# WEN-OP-AD8367.net
KiCad netlist of a schematic drawn in EasyEDA Pro
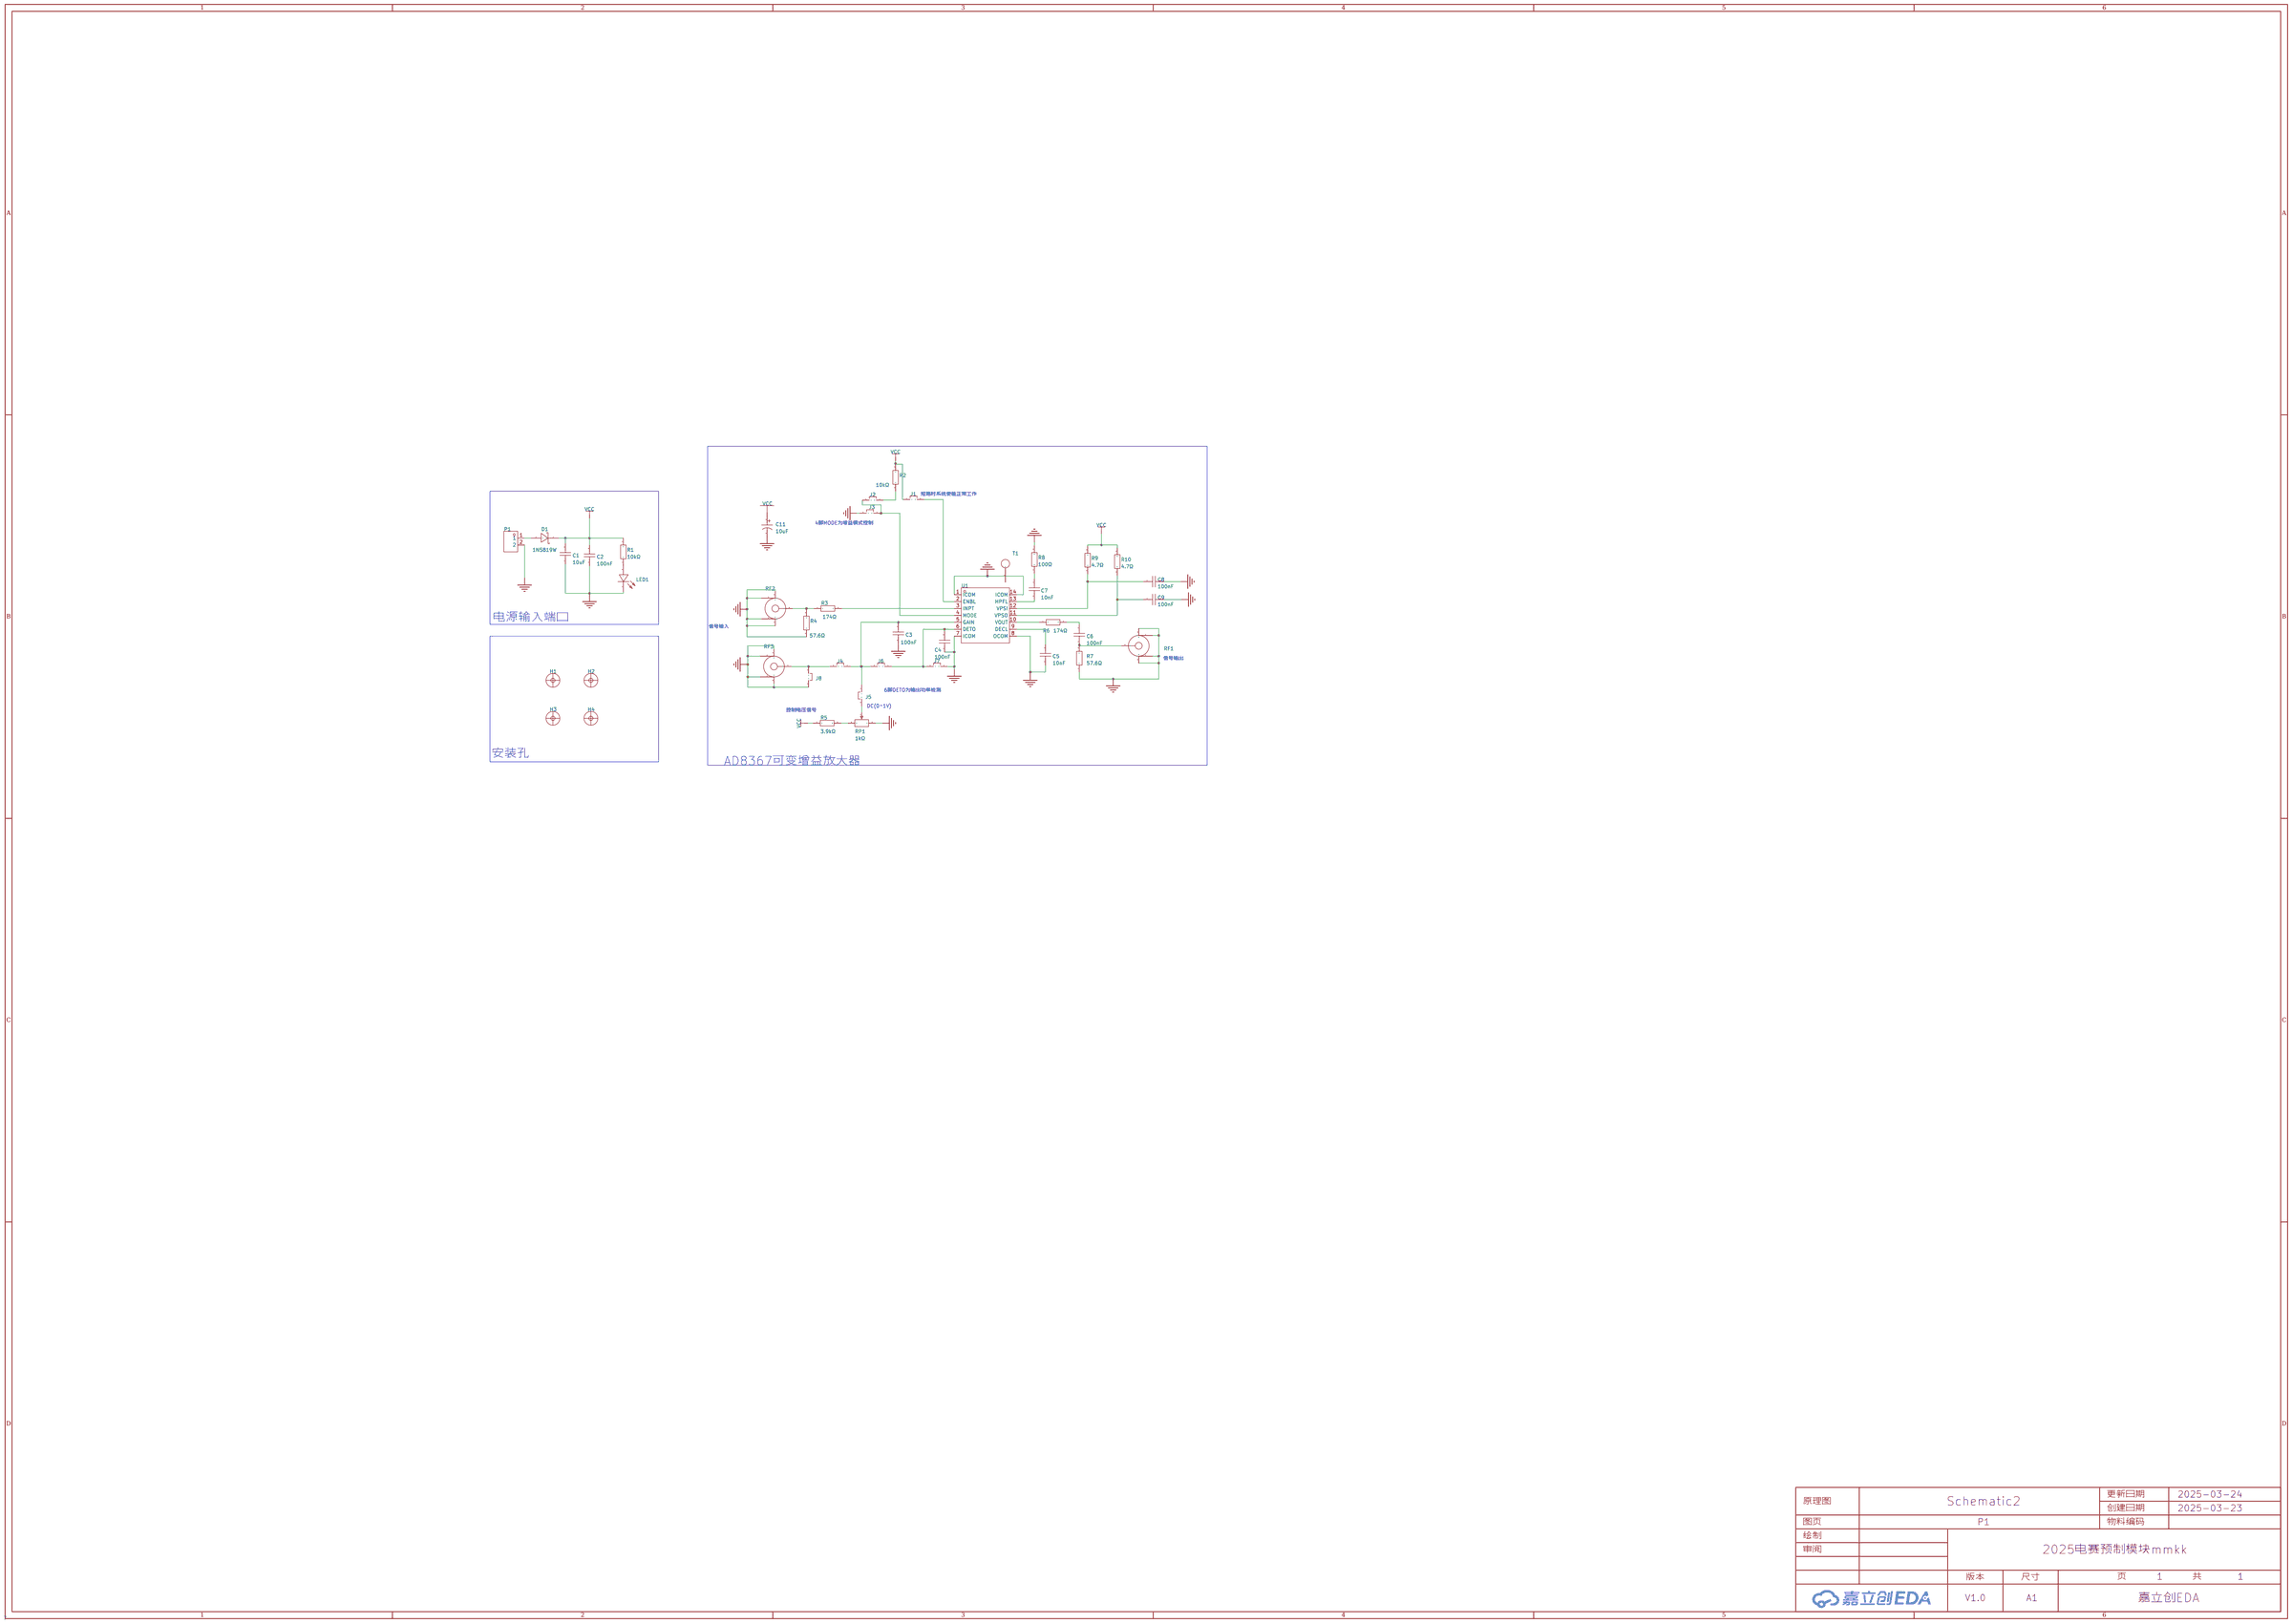
[diagram p0: schematic sheet]

(export (version "E")
  (design (tool "Eeschema 10.0.6"))
  (components
    (comp (ref "C1")
      (value "10uF")
      (footprint "easyedapro:C0805")
      (description "容值:10uF;精度:±10%;额定电压:25V;材质(温度系数):X5R;")
      (fields
        (field (name "Manufacturer Part") "CL21A106KAYNNNE")
        (field (name "Manufacturer") "SAMSUNG(三星)")
      )
      (libsource (lib "easyedapro") (part "CL21A106KAYNNNE"))
    )
    (comp (ref "C2")
      (value "100nF")
      (footprint "easyedapro:C0805")
      (description "容值:100nF;精度:±10%;额定电压:100V;材质(温度系数):X7R;")
      (fields
        (field (name "Manufacturer Part") "CL21B104KCFNNNE")
        (field (name "Manufacturer") "SAMSUNG(三星)")
      )
      (libsource (lib "easyedapro") (part "CL21B104KCFNNNE"))
    )
    (comp (ref "C3")
      (value "100nF")
      (footprint "easyedapro:C0805")
      (description "容值:100nF;精度:±10%;额定电压:100V;材质(温度系数):X7R;")
      (fields
        (field (name "Manufacturer Part") "CL21B104KCFNNNE")
        (field (name "Manufacturer") "SAMSUNG(三星)")
      )
      (libsource (lib "easyedapro") (part "CL21B104KCFNNNE"))
    )
    (comp (ref "C4")
      (value "100nF")
      (footprint "easyedapro:C0805")
      (description "容值:100nF;精度:±10%;额定电压:100V;材质(温度系数):X7R;")
      (fields
        (field (name "Manufacturer Part") "CL21B104KCFNNNE")
        (field (name "Manufacturer") "SAMSUNG(三星)")
      )
      (libsource (lib "easyedapro") (part "CL21B104KCFNNNE"))
    )
    (comp (ref "C5")
      (value "10nF")
      (footprint "easyedapro:C0805")
      (description "容值:10nF;精度:±10%;额定电压:50V;材质(温度系数):X7R;")
      (fields
        (field (name "Manufacturer Part") "CL21B103KBANNNC")
        (field (name "Manufacturer") "SAMSUNG(三星)")
      )
      (libsource (lib "easyedapro") (part "CL21B103KBANNNC"))
    )
    (comp (ref "C6")
      (value "100nF")
      (footprint "easyedapro:C0805")
      (description "容值:100nF;精度:±10%;额定电压:100V;材质(温度系数):X7R;")
      (fields
        (field (name "Manufacturer Part") "CL21B104KCFNNNE")
        (field (name "Manufacturer") "SAMSUNG(三星)")
      )
      (libsource (lib "easyedapro") (part "CL21B104KCFNNNE"))
    )
    (comp (ref "C7")
      (value "10nF")
      (footprint "easyedapro:C0805")
      (description "容值:10nF;精度:±10%;额定电压:50V;材质(温度系数):X7R;")
      (fields
        (field (name "Manufacturer Part") "CL21B103KBANNNC")
        (field (name "Manufacturer") "SAMSUNG(三星)")
      )
      (libsource (lib "easyedapro") (part "CL21B103KBANNNC"))
    )
    (comp (ref "C8")
      (value "100nF")
      (footprint "easyedapro:C0805")
      (description "容值:100nF;精度:±10%;额定电压:100V;材质(温度系数):X7R;")
      (fields
        (field (name "Manufacturer Part") "CL21B104KCFNNNE")
        (field (name "Manufacturer") "SAMSUNG(三星)")
      )
      (libsource (lib "easyedapro") (part "CL21B104KCFNNNE"))
    )
    (comp (ref "C9")
      (value "100nF")
      (footprint "easyedapro:C0805")
      (description "容值:100nF;精度:±10%;额定电压:100V;材质(温度系数):X7R;")
      (fields
        (field (name "Manufacturer Part") "CL21B104KCFNNNE")
        (field (name "Manufacturer") "SAMSUNG(三星)")
      )
      (libsource (lib "easyedapro") (part "CL21B104KCFNNNE"))
    )
    (comp (ref "C11")
      (value "10uF")
      (footprint "easyedapro:CAP-SMD_BD4.0-L4.3-W4.3-FD")
      (fields (field (name "Manufacturer Part") "CS1C100M-CRC54") (field (name "Manufacturer") "ST(先科)"))
      (libsource (lib "easyedapro") (part "CS1C100M-CRC54"))
    )
    (comp (ref "D1")
      (value "1N5819W")
      (footprint "easyedapro:SOD-123F_L2.8-W1.8-LS3.7-RD")
      (description "直流反向耐压(Vr):40V;平均整流电流(Io):1A;正向压降(Vf):600mV@1A;")
      (fields (field (name "Manufacturer") "晶导微电子"))
      (libsource (lib "easyedapro") (part "1N5819W"))
    )
    (comp (ref "H1")
      (value "~")
      (footprint "easyedapro:M3")
      (fields (field (name "Manufacturer Part") "M3x10+6") (field (name "Manufacturer") "Shuntian(顺天五金)"))
      (libsource (lib "easyedapro") (part "M3"))
    )
    (comp (ref "H2")
      (value "~")
      (footprint "easyedapro:M3")
      (fields (field (name "Manufacturer Part") "M3x10+6") (field (name "Manufacturer") "Shuntian(顺天五金)"))
      (libsource (lib "easyedapro") (part "M3"))
    )
    (comp (ref "H3")
      (value "~")
      (footprint "easyedapro:M3")
      (fields (field (name "Manufacturer Part") "M3x10+6") (field (name "Manufacturer") "Shuntian(顺天五金)"))
      (libsource (lib "easyedapro") (part "M3"))
    )
    (comp (ref "H4")
      (value "~")
      (footprint "easyedapro:M3")
      (fields (field (name "Manufacturer Part") "M3x10+6") (field (name "Manufacturer") "Shuntian(顺天五金)"))
      (libsource (lib "easyedapro") (part "M3"))
    )
    (comp (ref "J1")
      (value "PZ254V-11-02P")
      (footprint "easyedapro:HDR-TH_2P-P2.54-V-M")
      (fields (field (name "Manufacturer") "XFCN(兴飞)"))
      (libsource (lib "easyedapro") (part "PZ254V-11-02P"))
    )
    (comp (ref "J2")
      (value "PZ254V-11-02P")
      (footprint "easyedapro:HDR-TH_2P-P2.54-V-M")
      (fields (field (name "Manufacturer") "XFCN(兴飞)"))
      (libsource (lib "easyedapro") (part "PZ254V-11-02P"))
    )
    (comp (ref "J3")
      (value "PZ254V-11-02P")
      (footprint "easyedapro:HDR-TH_2P-P2.54-V-M")
      (fields (field (name "Manufacturer") "XFCN(兴飞)"))
      (libsource (lib "easyedapro") (part "PZ254V-11-02P"))
    )
    (comp (ref "J4")
      (value "PZ254V-11-02P")
      (footprint "easyedapro:HDR-TH_2P-P2.54-V-M")
      (fields (field (name "Manufacturer") "XFCN(兴飞)"))
      (libsource (lib "easyedapro") (part "PZ254V-11-02P"))
    )
    (comp (ref "J5")
      (value "PZ254V-11-02P")
      (footprint "easyedapro:HDR-TH_2P-P2.54-V-M")
      (fields (field (name "Manufacturer") "XFCN(兴飞)"))
      (libsource (lib "easyedapro") (part "PZ254V-11-02P"))
    )
    (comp (ref "J6")
      (value "PZ254V-11-02P")
      (footprint "easyedapro:HDR-TH_2P-P2.54-V-M")
      (fields (field (name "Manufacturer") "XFCN(兴飞)"))
      (libsource (lib "easyedapro") (part "PZ254V-11-02P"))
    )
    (comp (ref "J7")
      (value "PZ254V-11-02P")
      (footprint "easyedapro:HDR-TH_2P-P2.54-V-M")
      (fields (field (name "Manufacturer") "XFCN(兴飞)"))
      (libsource (lib "easyedapro") (part "PZ254V-11-02P"))
    )
    (comp (ref "J8")
      (value "PZ254V-11-02P")
      (footprint "easyedapro:HDR-TH_2P-P2.54-V-M")
      (fields (field (name "Manufacturer") "XFCN(兴飞)"))
      (libsource (lib "easyedapro") (part "PZ254V-11-02P"))
    )
    (comp (ref "LED1")
      (value "NCD0805R1")
      (footprint "easyedapro:LED0805-RD_RED")
      (description "发光颜色:红灯;")
      (fields (field (name "Manufacturer") "国星光电"))
      (libsource (lib "easyedapro") (part "FC-2012HRK-620D"))
    )
    (comp (ref "P1")
      (value "KF301-5.0-2P")
      (footprint "easyedapro:CONN-TH_P5.00_KF301-5.0-2P")
      (fields (field (name "Manufacturer") "KEFA(科发)"))
      (libsource (lib "easyedapro") (part "KF301-5.0-2P"))
    )
    (comp (ref "R1")
      (value "10kΩ")
      (footprint "easyedapro:R0805")
      (description "电阻类型:厚膜电阻;阻值:10kΩ;精度:±1%;功率:125mW;")
      (fields
        (field (name "Manufacturer Part") "0805W8F1002T5E")
        (field (name "Manufacturer") "UNI-ROYAL(厚声)")
      )
      (libsource (lib "easyedapro") (part "0805W8F1002T5E"))
    )
    (comp (ref "R2")
      (value "10kΩ")
      (footprint "easyedapro:R0805")
      (description "电阻类型:厚膜电阻;阻值:10kΩ;精度:±1%;功率:125mW;")
      (fields
        (field (name "Manufacturer Part") "0805W8F1002T5E")
        (field (name "Manufacturer") "UNI-ROYAL(厚声)")
      )
      (libsource (lib "easyedapro") (part "0805W8F1002T5E"))
    )
    (comp (ref "R3")
      (value "174Ω")
      (footprint "easyedapro:R0805")
      (description "电阻类型:厚膜电阻;阻值:174Ω;精度:±1%;功率:125mW;")
      (fields
        (field (name "Manufacturer Part") "0805W8F1740T5E")
        (field (name "Manufacturer") "UNI-ROYAL(厚声)")
      )
      (libsource (lib "easyedapro") (part "0805W8F1740T5E"))
    )
    (comp (ref "R4")
      (value "57.6Ω")
      (footprint "easyedapro:R0805")
      (description "电阻类型:厚膜电阻;阻值:57.6Ω;精度:±1%;功率:125mW;")
      (fields
        (field (name "Manufacturer Part") "0805W8F576JT5E")
        (field (name "Manufacturer") "UNI-ROYAL(厚声)")
      )
      (libsource (lib "easyedapro") (part "0805W8F576JT5E"))
    )
    (comp (ref "R5")
      (value "3.9kΩ")
      (footprint "easyedapro:R0805")
      (description "电阻类型:厚膜电阻;阻值:3.9kΩ;精度:±1%;功率:125mW;")
      (fields
        (field (name "Manufacturer Part") "0805W8F3901T5E")
        (field (name "Manufacturer") "UNI-ROYAL(厚声)")
      )
      (libsource (lib "easyedapro") (part "0805W8F3901T5E"))
    )
    (comp (ref "R6")
      (value "174Ω")
      (footprint "easyedapro:R0805")
      (description "电阻类型:厚膜电阻;阻值:174Ω;精度:±1%;功率:125mW;")
      (fields
        (field (name "Manufacturer Part") "0805W8F1740T5E")
        (field (name "Manufacturer") "UNI-ROYAL(厚声)")
      )
      (libsource (lib "easyedapro") (part "0805W8F1740T5E"))
    )
    (comp (ref "R7")
      (value "57.6Ω")
      (footprint "easyedapro:R0805")
      (description "电阻类型:厚膜电阻;阻值:57.6Ω;精度:±1%;功率:125mW;")
      (fields
        (field (name "Manufacturer Part") "0805W8F576JT5E")
        (field (name "Manufacturer") "UNI-ROYAL(厚声)")
      )
      (libsource (lib "easyedapro") (part "0805W8F576JT5E"))
    )
    (comp (ref "R8")
      (value "100Ω")
      (footprint "easyedapro:R0805")
      (description "电阻类型:厚膜电阻;阻值:100Ω;精度:±1%;功率:125mW;")
      (fields
        (field (name "Manufacturer Part") "0805W8F1000T5E")
        (field (name "Manufacturer") "UNI-ROYAL(厚声)")
      )
      (libsource (lib "easyedapro") (part "0805W8F1000T5E"))
    )
    (comp (ref "R9")
      (value "4.7Ω")
      (footprint "easyedapro:R0805")
      (description "电阻类型:厚膜电阻;阻值:4.7Ω;精度:±1%;功率:125mW;")
      (fields
        (field (name "Manufacturer Part") "0805W8F470KT5E")
        (field (name "Manufacturer") "UNI-ROYAL(厚声)")
      )
      (libsource (lib "easyedapro") (part "0805W8F470KT5E"))
    )
    (comp (ref "R10")
      (value "4.7Ω")
      (footprint "easyedapro:R0805")
      (description "电阻类型:厚膜电阻;阻值:4.7Ω;精度:±1%;功率:125mW;")
      (fields
        (field (name "Manufacturer Part") "0805W8F470KT5E")
        (field (name "Manufacturer") "UNI-ROYAL(厚声)")
      )
      (libsource (lib "easyedapro") (part "0805W8F470KT5E"))
    )
    (comp (ref "RF1")
      (value "BWSMA-KE-P001")
      (footprint "easyedapro:SMA-SMD_BWSMA-KE-P001")
      (description "连接器类型:板端;射频系列:SMA;接口类型:内孔;端口数量:1;阻抗:50Ω;频率-最大值:12.4GHz;样式:偏脚;接口直径:5.2mm;接口长度/高度:-;工作温度范围:-;")
      (fields (field (name "Manufacturer") "BAT WIRELESS(蝙蝠无线)"))
      (libsource (lib "easyedapro") (part "BWSMA-KE-P001"))
    )
    (comp (ref "RF2")
      (value "BWSMA-KE-P001")
      (footprint "easyedapro:SMA-SMD_BWSMA-KE-P001")
      (description "连接器类型:板端;射频系列:SMA;接口类型:内孔;端口数量:1;阻抗:50Ω;频率-最大值:12.4GHz;样式:偏脚;接口直径:5.2mm;接口长度/高度:-;工作温度范围:-;")
      (fields (field (name "Manufacturer") "BAT WIRELESS(蝙蝠无线)"))
      (libsource (lib "easyedapro") (part "BWSMA-KE-P001"))
    )
    (comp (ref "RF3")
      (value "BWSMA-KE-P001")
      (footprint "easyedapro:SMA-SMD_BWSMA-KE-P001")
      (description "连接器类型:板端;射频系列:SMA;接口类型:内孔;端口数量:1;阻抗:50Ω;频率-最大值:12.4GHz;样式:偏脚;接口直径:5.2mm;接口长度/高度:-;工作温度范围:-;")
      (fields (field (name "Manufacturer") "BAT WIRELESS(蝙蝠无线)"))
      (libsource (lib "easyedapro") (part "BWSMA-KE-P001"))
    )
    (comp (ref "RP1")
      (value "1kΩ")
      (footprint "easyedapro:RES-ADJ-TH_3P-L10.0-W10.0-P2.50-BL-BS")
      (description "阻值:1kΩ;精度:±10%;")
      (fields (field (name "Manufacturer Part") "3296W-1-102") (field (name "Manufacturer") "BOCHEN(博晨)"))
      (libsource (lib "easyedapro") (part "3296W-1-102"))
    )
    (comp (ref "T1") (value "~") (footprint "easyedapro:测试环") (libsource (lib "easyedapro") (part "测试环")))
    (comp (ref "U1")
      (value "AD8367ARUZ-RL7")
      (footprint "easyedapro:TSSOP-14_L5.0-W4.4-P0.65-LS6.4-BL")
      (fields (field (name "Manufacturer") "ADI(亚德诺)/LINEAR(凌特)"))
      (libsource (lib "easyedapro") (part "AD8367ARUZ-RL7"))
    )
  )
  (nets
    (net (code "1") (name "GND") (class "Default")
      (node (ref "C1") (pin "1") (pinfunction "1_1") (pintype "input"))
      (node (ref "C11") (pin "2") (pinfunction "2_2") (pintype "input"))
      (node (ref "C2") (pin "1") (pinfunction "1_1") (pintype "input"))
      (node (ref "C3") (pin "1") (pinfunction "1_1") (pintype "input"))
      (node (ref "C4") (pin "1") (pinfunction "1_1") (pintype "input"))
      (node (ref "C5") (pin "1") (pinfunction "1_1") (pintype "input"))
      (node (ref "C8") (pin "1") (pinfunction "1_1") (pintype "input"))
      (node (ref "C9") (pin "1") (pinfunction "1_1") (pintype "input"))
      (node (ref "J3") (pin "2") (pinfunction "2_2") (pintype "input"))
      (node (ref "J7") (pin "1") (pinfunction "1_1") (pintype "input"))
      (node (ref "J8") (pin "1") (pinfunction "1_1") (pintype "input"))
      (node (ref "LED1") (pin "1") (pinfunction "-_1") (pintype "input"))
      (node (ref "P1") (pin "2") (pinfunction "2_2") (pintype "input"))
      (node (ref "R4") (pin "1") (pinfunction "1_1") (pintype "input"))
      (node (ref "R7") (pin "1") (pinfunction "1_1") (pintype "input"))
      (node (ref "R8") (pin "2") (pinfunction "2_2") (pintype "input"))
      (node (ref "RF1") (pin "1") (pinfunction "1_1") (pintype "input"))
      (node (ref "RF1") (pin "2") (pinfunction "2_2") (pintype "input"))
      (node (ref "RF1") (pin "3") (pinfunction "3_3") (pintype "input"))
      (node (ref "RF1") (pin "4") (pinfunction "4_4") (pintype "input"))
      (node (ref "RF2") (pin "1") (pinfunction "1_1") (pintype "input"))
      (node (ref "RF2") (pin "2") (pinfunction "2_2") (pintype "input"))
      (node (ref "RF2") (pin "3") (pinfunction "3_3") (pintype "input"))
      (node (ref "RF2") (pin "4") (pinfunction "4_4") (pintype "input"))
      (node (ref "RF3") (pin "1") (pinfunction "1_1") (pintype "input"))
      (node (ref "RF3") (pin "2") (pinfunction "2_2") (pintype "input"))
      (node (ref "RF3") (pin "3") (pinfunction "3_3") (pintype "input"))
      (node (ref "RF3") (pin "4") (pinfunction "4_4") (pintype "input"))
      (node (ref "RP1") (pin "1") (pinfunction "1_1") (pintype "input"))
      (node (ref "U1") (pin "1") (pinfunction "ICOM_1") (pintype "input"))
      (node (ref "U1") (pin "14") (pinfunction "ICOM_14") (pintype "input"))
      (node (ref "U1") (pin "7") (pinfunction "ICOM_7") (pintype "input"))
      (node (ref "U1") (pin "8") (pinfunction "OCOM_8") (pintype "input"))
    )
    (net (code "2") (name "Net-(C6-Pad1)") (class "Default")
      (node (ref "C6") (pin "1") (pinfunction "1_1") (pintype "input"))
      (node (ref "R7") (pin "2") (pinfunction "2_2") (pintype "input"))
      (node (ref "RF1") (pin "5") (pinfunction "5_5") (pintype "input"))
    )
    (net (code "3") (name "Net-(C6-Pad2)") (class "Default")
      (node (ref "C6") (pin "2") (pinfunction "2_2") (pintype "input"))
      (node (ref "R6") (pin "2") (pinfunction "2_2") (pintype "input"))
    )
    (net (code "4") (name "Net-(C7-Pad1)") (class "Default")
      (node (ref "C7") (pin "1") (pinfunction "1_1") (pintype "input"))
      (node (ref "R8") (pin "1") (pinfunction "1_1") (pintype "input"))
    )
    (net (code "5") (name "Net-(D1-Pad2)") (class "Default")
      (node (ref "D1") (pin "2") (pinfunction "2_2") (pintype "input"))
      (node (ref "P1") (pin "1") (pinfunction "1_1") (pintype "input"))
    )
    (net (code "6") (name "Net-(J2-Pad1)") (class "Default")
      (node (ref "J2") (pin "1") (pinfunction "1_1") (pintype "input"))
      (node (ref "R2") (pin "1") (pinfunction "1_1") (pintype "input"))
    )
    (net (code "7") (name "Net-(J4-Pad2)") (class "Default")
      (node (ref "J4") (pin "2") (pinfunction "2_2") (pintype "input"))
      (node (ref "J8") (pin "2") (pinfunction "2_2") (pintype "input"))
      (node (ref "RF3") (pin "5") (pinfunction "5_5") (pintype "input"))
    )
    (net (code "8") (name "Net-(J5-Pad2)") (class "Default")
      (node (ref "J5") (pin "2") (pinfunction "2_2") (pintype "input"))
      (node (ref "RP1") (pin "2") (pinfunction "2_2") (pintype "input"))
    )
    (net (code "9") (name "Net-(LED1-+)") (class "Default")
      (node (ref "LED1") (pin "2") (pinfunction "+_2") (pintype "input"))
      (node (ref "R1") (pin "1") (pinfunction "1_1") (pintype "input"))
    )
    (net (code "10") (name "Net-(R3-Pad1)") (class "Default")
      (node (ref "R3") (pin "1") (pinfunction "1_1") (pintype "input"))
      (node (ref "R4") (pin "2") (pinfunction "2_2") (pintype "input"))
      (node (ref "RF2") (pin "5") (pinfunction "5_5") (pintype "input"))
    )
    (net (code "11") (name "Net-(R5-Pad2)") (class "Default")
      (node (ref "R5") (pin "2") (pinfunction "2_2") (pintype "input"))
      (node (ref "RP1") (pin "3") (pinfunction "3_3") (pintype "input"))
    )
    (net (code "12") (name "Net-(U1-DECL)") (class "Default")
      (node (ref "C5") (pin "2") (pinfunction "2_2") (pintype "input"))
      (node (ref "U1") (pin "9") (pinfunction "DECL_9") (pintype "input"))
    )
    (net (code "13") (name "Net-(U1-DETO)") (class "Default")
      (node (ref "C4") (pin "2") (pinfunction "2_2") (pintype "input"))
      (node (ref "J6") (pin "1") (pinfunction "1_1") (pintype "input"))
      (node (ref "J7") (pin "2") (pinfunction "2_2") (pintype "input"))
      (node (ref "U1") (pin "6") (pinfunction "DETO_6") (pintype "input"))
    )
    (net (code "14") (name "Net-(U1-ENBL)") (class "Default")
      (node (ref "J1") (pin "2") (pinfunction "2_2") (pintype "input"))
      (node (ref "U1") (pin "2") (pinfunction "ENBL_2") (pintype "input"))
    )
    (net (code "15") (name "Net-(U1-GAIN)") (class "Default")
      (node (ref "C3") (pin "2") (pinfunction "2_2") (pintype "input"))
      (node (ref "J4") (pin "1") (pinfunction "1_1") (pintype "input"))
      (node (ref "J5") (pin "1") (pinfunction "1_1") (pintype "input"))
      (node (ref "J6") (pin "2") (pinfunction "2_2") (pintype "input"))
      (node (ref "U1") (pin "5") (pinfunction "GAIN_5") (pintype "input"))
    )
    (net (code "16") (name "Net-(U1-HPFL)") (class "Default")
      (node (ref "C7") (pin "2") (pinfunction "2_2") (pintype "input"))
      (node (ref "U1") (pin "13") (pinfunction "HPFL_13") (pintype "input"))
    )
    (net (code "17") (name "Net-(U1-INPT)") (class "Default")
      (node (ref "R3") (pin "2") (pinfunction "2_2") (pintype "input"))
      (node (ref "U1") (pin "3") (pinfunction "INPT_3") (pintype "input"))
    )
    (net (code "18") (name "Net-(U1-MODE)") (class "Default")
      (node (ref "J2") (pin "2") (pinfunction "2_2") (pintype "input"))
      (node (ref "J3") (pin "1") (pinfunction "1_1") (pintype "input"))
      (node (ref "U1") (pin "4") (pinfunction "MODE_4") (pintype "input"))
    )
    (net (code "19") (name "Net-(U1-VOUT)") (class "Default")
      (node (ref "R6") (pin "1") (pinfunction "1_1") (pintype "input"))
      (node (ref "U1") (pin "10") (pinfunction "VOUT_10") (pintype "input"))
    )
    (net (code "20") (name "Net-(U1-VPSI)") (class "Default")
      (node (ref "C8") (pin "2") (pinfunction "2_2") (pintype "input"))
      (node (ref "R9") (pin "1") (pinfunction "1_1") (pintype "input"))
      (node (ref "U1") (pin "12") (pinfunction "VPSI_12") (pintype "input"))
    )
    (net (code "21") (name "Net-(U1-VPSO)") (class "Default")
      (node (ref "C9") (pin "2") (pinfunction "2_2") (pintype "input"))
      (node (ref "R10") (pin "1") (pinfunction "1_1") (pintype "input"))
      (node (ref "U1") (pin "11") (pinfunction "VPSO_11") (pintype "input"))
    )
    (net (code "22") (name "VCC") (class "Default")
      (node (ref "C1") (pin "2") (pinfunction "2_2") (pintype "input"))
      (node (ref "C11") (pin "1") (pinfunction "1_1") (pintype "input"))
      (node (ref "C2") (pin "2") (pinfunction "2_2") (pintype "input"))
      (node (ref "D1") (pin "1") (pinfunction "1_1") (pintype "input"))
      (node (ref "J1") (pin "1") (pinfunction "1_1") (pintype "input"))
      (node (ref "R1") (pin "2") (pinfunction "2_2") (pintype "input"))
      (node (ref "R10") (pin "2") (pinfunction "2_2") (pintype "input"))
      (node (ref "R2") (pin "2") (pinfunction "2_2") (pintype "input"))
      (node (ref "R5") (pin "1") (pinfunction "1_1") (pintype "input"))
      (node (ref "R9") (pin "2") (pinfunction "2_2") (pintype "input"))
    )
    (net (code "23") (name "unconnected-(T1-Pad1)") (class "Default")
      (node (ref "T1") (pin "1") (pinfunction "1_1") (pintype "input"))
    )
  )
)
